# HalfBridge_MOSFET.net
KiCad netlist of a schematic drawn in Altium Designer
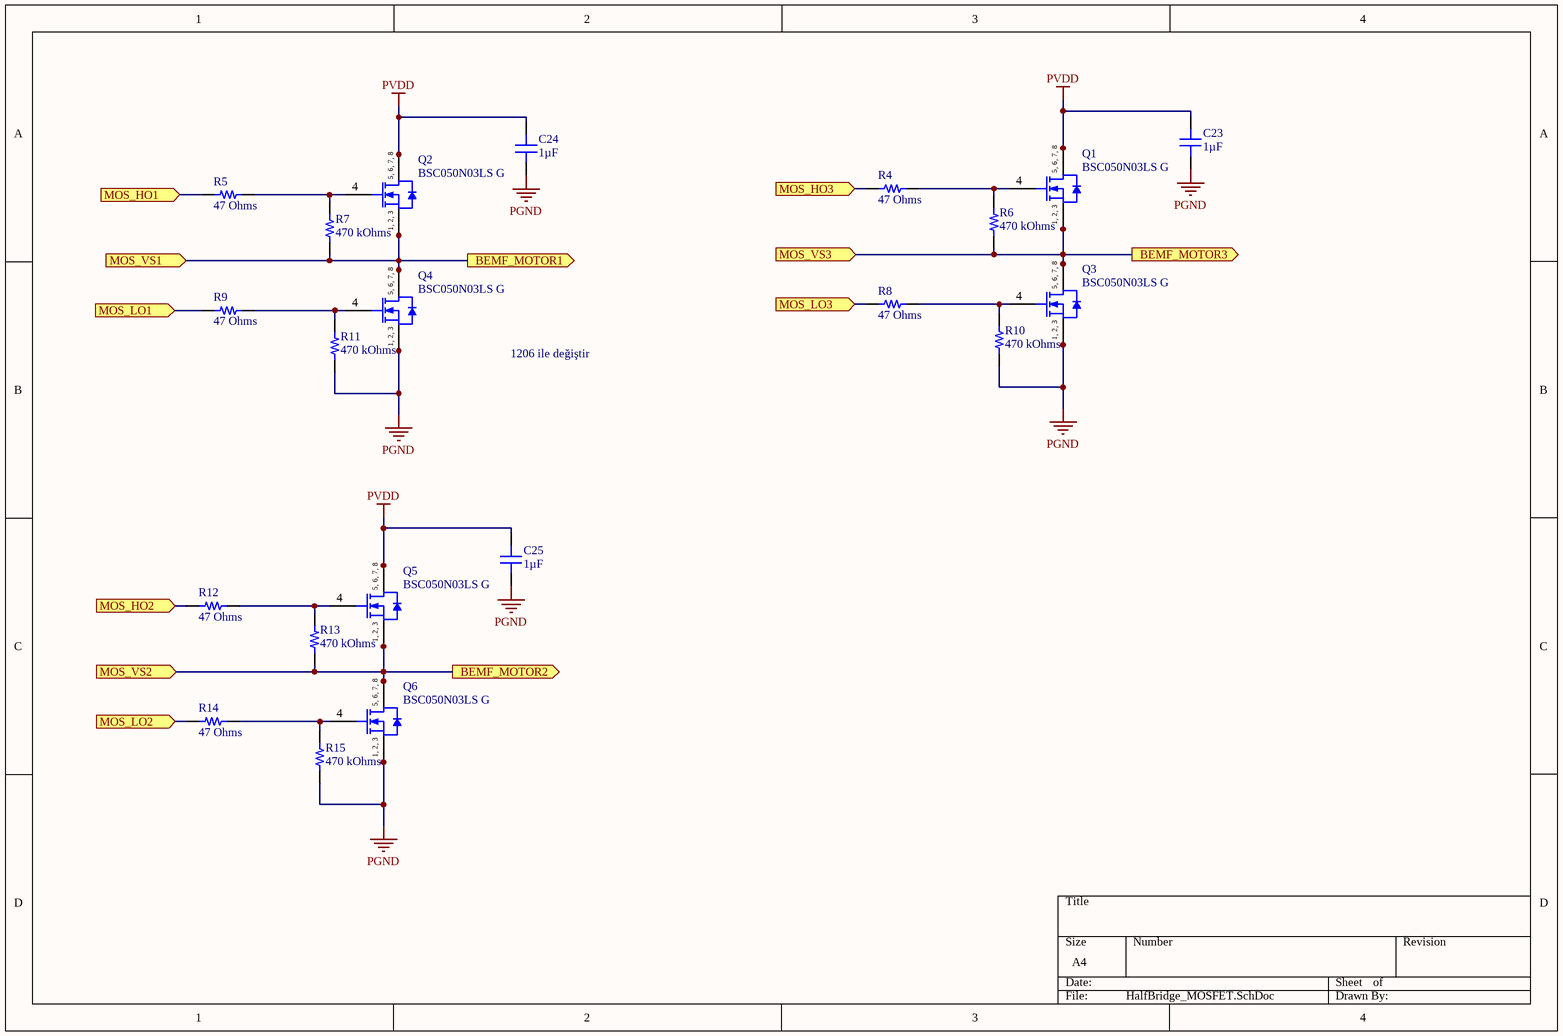
[diagram p0: HalfBridge_MOSFET.SchDoc]

(export (version "E")
  (design (tool "Eeschema 10.0.6"))
  (components
    (comp (ref "C23")
      (value "1µF")
      (footprint "CAP 1206_3216 - 1.8MM")
      (description "CAP CER 1UF 100V X7R 1206")
      (fields (field (name "PART NUMBER") "HMK316B7105KLHT") (field (name "MANUFACTURER") "Taiyo Yuden"))
      (libsource (lib "Celestial Altium Library - altium_library") (part "Capacitor"))
    )
    (comp (ref "C24")
      (value "1µF")
      (footprint "CAP 1206_3216 - 1.8MM")
      (description "CAP CER 1UF 100V X7R 1206")
      (fields (field (name "PART NUMBER") "HMK316B7105KLHT") (field (name "MANUFACTURER") "Taiyo Yuden"))
      (libsource (lib "Celestial Altium Library - altium_library") (part "Capacitor"))
    )
    (comp (ref "C25")
      (value "1µF")
      (footprint "CAP 1206_3216 - 1.8MM")
      (description "CAP CER 1UF 100V X7R 1206")
      (fields (field (name "PART NUMBER") "HMK316B7105KLHT") (field (name "MANUFACTURER") "Taiyo Yuden"))
      (libsource (lib "Celestial Altium Library - altium_library") (part "Capacitor"))
    )
    (comp (ref "Q1")
      (value "BSC050N03LS G")
      (footprint "INF-PG-TDSON-8-1_V")
      (description "N-Channel OptiMOS 3 Power-MOSFET, 30 V VDS, 79 A ID, -55 to 150 degC, PG-TDSON-8-1, Reel, Green")
      (fields (field (name "MANUFACTURER") "Infineon"))
      (libsource (lib "UserIntegrated") (part "BSC050N03LS G_1"))
    )
    (comp (ref "Q2")
      (value "BSC050N03LS G")
      (footprint "INF-PG-TDSON-8-1_V")
      (description "N-Channel OptiMOS 3 Power-MOSFET, 30 V VDS, 79 A ID, -55 to 150 degC, PG-TDSON-8-1, Reel, Green")
      (fields (field (name "MANUFACTURER") "Infineon"))
      (libsource (lib "UserIntegrated") (part "BSC050N03LS G_1"))
    )
    (comp (ref "Q3")
      (value "BSC050N03LS G")
      (footprint "INF-PG-TDSON-8-1_V")
      (description "N-Channel OptiMOS 3 Power-MOSFET, 30 V VDS, 79 A ID, -55 to 150 degC, PG-TDSON-8-1, Reel, Green")
      (fields (field (name "MANUFACTURER") "Infineon"))
      (libsource (lib "UserIntegrated") (part "BSC050N03LS G_1"))
    )
    (comp (ref "Q4")
      (value "BSC050N03LS G")
      (footprint "INF-PG-TDSON-8-1_V")
      (description "N-Channel OptiMOS 3 Power-MOSFET, 30 V VDS, 79 A ID, -55 to 150 degC, PG-TDSON-8-1, Reel, Green")
      (fields (field (name "MANUFACTURER") "Infineon"))
      (libsource (lib "UserIntegrated") (part "BSC050N03LS G_1"))
    )
    (comp (ref "Q5")
      (value "BSC050N03LS G")
      (footprint "INF-PG-TDSON-8-1_V")
      (description "N-Channel OptiMOS 3 Power-MOSFET, 30 V VDS, 79 A ID, -55 to 150 degC, PG-TDSON-8-1, Reel, Green")
      (fields (field (name "MANUFACTURER") "Infineon"))
      (libsource (lib "UserIntegrated") (part "BSC050N03LS G_1"))
    )
    (comp (ref "Q6")
      (value "BSC050N03LS G")
      (footprint "INF-PG-TDSON-8-1_V")
      (description "N-Channel OptiMOS 3 Power-MOSFET, 30 V VDS, 79 A ID, -55 to 150 degC, PG-TDSON-8-1, Reel, Green")
      (fields (field (name "MANUFACTURER") "Infineon"))
      (libsource (lib "UserIntegrated") (part "BSC050N03LS G_1"))
    )
    (comp (ref "R4")
      (value "47 Ohms")
      (footprint "RES 1206_3216")
      (description "RES SMD 47 OHM 5% 1/4W 1206")
      (fields (field (name "PART NUMBER") "CRCW120647R0JNEAIF") (field (name "MANUFACTURER") "Vishay Dale"))
      (libsource (lib "Celestial Altium Library - altium_library") (part "Resistor"))
    )
    (comp (ref "R5")
      (value "47 Ohms")
      (footprint "RES 1206_3216")
      (description "RES SMD 47 OHM 5% 1/4W 1206")
      (fields (field (name "PART NUMBER") "CRCW120647R0JNEAIF") (field (name "MANUFACTURER") "Vishay Dale"))
      (libsource (lib "Celestial Altium Library - altium_library") (part "Resistor"))
    )
    (comp (ref "R6")
      (value "470 kOhms")
      (footprint "RES 1206_3216")
      (description "RES SMD 470K OHM 1% 1/4W 1206")
      (fields (field (name "PART NUMBER") "CRCW1206470KFKEA") (field (name "MANUFACTURER") "Vishay Dale"))
      (libsource (lib "Celestial Altium Library - altium_library") (part "Resistor"))
    )
    (comp (ref "R7")
      (value "470 kOhms")
      (footprint "RES 1206_3216")
      (description "RES SMD 470K OHM 1% 1/4W 1206")
      (fields (field (name "PART NUMBER") "CRCW1206470KFKEA") (field (name "MANUFACTURER") "Vishay Dale"))
      (libsource (lib "Celestial Altium Library - altium_library") (part "Resistor"))
    )
    (comp (ref "R8")
      (value "47 Ohms")
      (footprint "RES 1206_3216")
      (description "RES SMD 47 OHM 5% 1/4W 1206")
      (fields (field (name "PART NUMBER") "CRCW120647R0JNEAIF") (field (name "MANUFACTURER") "Vishay Dale"))
      (libsource (lib "Celestial Altium Library - altium_library") (part "Resistor"))
    )
    (comp (ref "R9")
      (value "47 Ohms")
      (footprint "RES 1206_3216")
      (description "RES SMD 47 OHM 5% 1/4W 1206")
      (fields (field (name "PART NUMBER") "CRCW120647R0JNEAIF") (field (name "MANUFACTURER") "Vishay Dale"))
      (libsource (lib "Celestial Altium Library - altium_library") (part "Resistor"))
    )
    (comp (ref "R10")
      (value "470 kOhms")
      (footprint "RES 1206_3216")
      (description "RES SMD 470K OHM 1% 1/4W 1206")
      (fields (field (name "PART NUMBER") "CRCW1206470KFKEA") (field (name "MANUFACTURER") "Vishay Dale"))
      (libsource (lib "Celestial Altium Library - altium_library") (part "Resistor"))
    )
    (comp (ref "R11")
      (value "470 kOhms")
      (footprint "RES 1206_3216")
      (description "RES SMD 470K OHM 1% 1/4W 1206")
      (fields (field (name "PART NUMBER") "CRCW1206470KFKEA") (field (name "MANUFACTURER") "Vishay Dale"))
      (libsource (lib "Celestial Altium Library - altium_library") (part "Resistor"))
    )
    (comp (ref "R12")
      (value "47 Ohms")
      (footprint "RES 1206_3216")
      (description "RES SMD 47 OHM 5% 1/4W 1206")
      (fields (field (name "PART NUMBER") "CRCW120647R0JNEAIF") (field (name "MANUFACTURER") "Vishay Dale"))
      (libsource (lib "Celestial Altium Library - altium_library") (part "Resistor"))
    )
    (comp (ref "R13")
      (value "470 kOhms")
      (footprint "RES 1206_3216")
      (description "RES SMD 470K OHM 1% 1/4W 1206")
      (fields (field (name "PART NUMBER") "CRCW1206470KFKEA") (field (name "MANUFACTURER") "Vishay Dale"))
      (libsource (lib "Celestial Altium Library - altium_library") (part "Resistor"))
    )
    (comp (ref "R14")
      (value "47 Ohms")
      (footprint "RES 1206_3216")
      (description "RES SMD 47 OHM 5% 1/4W 1206")
      (fields (field (name "PART NUMBER") "CRCW120647R0JNEAIF") (field (name "MANUFACTURER") "Vishay Dale"))
      (libsource (lib "Celestial Altium Library - altium_library") (part "Resistor"))
    )
    (comp (ref "R15")
      (value "470 kOhms")
      (footprint "RES 1206_3216")
      (description "RES SMD 470K OHM 1% 1/4W 1206")
      (fields (field (name "PART NUMBER") "CRCW1206470KFKEA") (field (name "MANUFACTURER") "Vishay Dale"))
      (libsource (lib "Celestial Altium Library - altium_library") (part "Resistor"))
    )
  )
  (nets
    (net (code "1") (name "/BEMF_MOTOR1") (class "Default")
      (node (ref "Q2") (pin "1") (pinfunction "SOURCE_1") (pintype "passive"))
      (node (ref "Q2") (pin "2") (pinfunction "SOURCE_2") (pintype "passive"))
      (node (ref "Q2") (pin "3") (pinfunction "SOURCE_3") (pintype "passive"))
      (node (ref "Q4") (pin "5") (pinfunction "DRAIN_5") (pintype "passive"))
      (node (ref "Q4") (pin "6") (pinfunction "DRAIN_6") (pintype "passive"))
      (node (ref "Q4") (pin "7") (pinfunction "DRAIN_7") (pintype "passive"))
      (node (ref "Q4") (pin "8") (pinfunction "DRAIN_8") (pintype "passive"))
      (node (ref "R7") (pin "1") (pinfunction "1_1") (pintype "passive"))
    )
    (net (code "2") (name "/BEMF_MOTOR2") (class "Default")
      (node (ref "Q5") (pin "1") (pinfunction "SOURCE_1") (pintype "passive"))
      (node (ref "Q5") (pin "2") (pinfunction "SOURCE_2") (pintype "passive"))
      (node (ref "Q5") (pin "3") (pinfunction "SOURCE_3") (pintype "passive"))
      (node (ref "Q6") (pin "5") (pinfunction "DRAIN_5") (pintype "passive"))
      (node (ref "Q6") (pin "6") (pinfunction "DRAIN_6") (pintype "passive"))
      (node (ref "Q6") (pin "7") (pinfunction "DRAIN_7") (pintype "passive"))
      (node (ref "Q6") (pin "8") (pinfunction "DRAIN_8") (pintype "passive"))
      (node (ref "R13") (pin "1") (pinfunction "1_1") (pintype "passive"))
    )
    (net (code "3") (name "/BEMF_MOTOR3") (class "Default")
      (node (ref "Q1") (pin "1") (pinfunction "SOURCE_1") (pintype "passive"))
      (node (ref "Q1") (pin "2") (pinfunction "SOURCE_2") (pintype "passive"))
      (node (ref "Q1") (pin "3") (pinfunction "SOURCE_3") (pintype "passive"))
      (node (ref "Q3") (pin "5") (pinfunction "DRAIN_5") (pintype "passive"))
      (node (ref "Q3") (pin "6") (pinfunction "DRAIN_6") (pintype "passive"))
      (node (ref "Q3") (pin "7") (pinfunction "DRAIN_7") (pintype "passive"))
      (node (ref "Q3") (pin "8") (pinfunction "DRAIN_8") (pintype "passive"))
      (node (ref "R6") (pin "1") (pinfunction "1_1") (pintype "passive"))
    )
    (net (code "4") (name "/MOS_HO1") (class "Default")
      (node (ref "R5") (pin "1") (pinfunction "1_1") (pintype "passive"))
    )
    (net (code "5") (name "/MOS_HO2") (class "Default")
      (node (ref "R12") (pin "1") (pinfunction "1_1") (pintype "passive"))
    )
    (net (code "6") (name "/MOS_HO3") (class "Default")
      (node (ref "R4") (pin "1") (pinfunction "1_1") (pintype "passive"))
    )
    (net (code "7") (name "/MOS_LO1") (class "Default")
      (node (ref "R9") (pin "1") (pinfunction "1_1") (pintype "passive"))
    )
    (net (code "8") (name "/MOS_LO2") (class "Default")
      (node (ref "R14") (pin "1") (pinfunction "1_1") (pintype "passive"))
    )
    (net (code "9") (name "/MOS_LO3") (class "Default")
      (node (ref "R8") (pin "1") (pinfunction "1_1") (pintype "passive"))
    )
    (net (code "10") (name "Net-(Q1-GATE)") (class "Default")
      (node (ref "Q1") (pin "4") (pinfunction "GATE_4") (pintype "passive"))
      (node (ref "R4") (pin "2") (pinfunction "2_2") (pintype "passive"))
      (node (ref "R6") (pin "2") (pinfunction "2_2") (pintype "passive"))
    )
    (net (code "11") (name "Net-(Q2-GATE)") (class "Default")
      (node (ref "Q2") (pin "4") (pinfunction "GATE_4") (pintype "passive"))
      (node (ref "R5") (pin "2") (pinfunction "2_2") (pintype "passive"))
      (node (ref "R7") (pin "2") (pinfunction "2_2") (pintype "passive"))
    )
    (net (code "12") (name "Net-(Q3-GATE)") (class "Default")
      (node (ref "Q3") (pin "4") (pinfunction "GATE_4") (pintype "passive"))
      (node (ref "R10") (pin "2") (pinfunction "2_2") (pintype "passive"))
      (node (ref "R8") (pin "2") (pinfunction "2_2") (pintype "passive"))
    )
    (net (code "13") (name "Net-(Q4-GATE)") (class "Default")
      (node (ref "Q4") (pin "4") (pinfunction "GATE_4") (pintype "passive"))
      (node (ref "R11") (pin "2") (pinfunction "2_2") (pintype "passive"))
      (node (ref "R9") (pin "2") (pinfunction "2_2") (pintype "passive"))
    )
    (net (code "14") (name "Net-(Q5-GATE)") (class "Default")
      (node (ref "Q5") (pin "4") (pinfunction "GATE_4") (pintype "passive"))
      (node (ref "R12") (pin "2") (pinfunction "2_2") (pintype "passive"))
      (node (ref "R13") (pin "2") (pinfunction "2_2") (pintype "passive"))
    )
    (net (code "15") (name "Net-(Q6-GATE)") (class "Default")
      (node (ref "Q6") (pin "4") (pinfunction "GATE_4") (pintype "passive"))
      (node (ref "R14") (pin "2") (pinfunction "2_2") (pintype "passive"))
      (node (ref "R15") (pin "2") (pinfunction "2_2") (pintype "passive"))
    )
    (net (code "16") (name "PGND") (class "Default")
      (node (ref "C23") (pin "1") (pinfunction "1_1") (pintype "passive"))
      (node (ref "C24") (pin "1") (pinfunction "1_1") (pintype "passive"))
      (node (ref "C25") (pin "1") (pinfunction "1_1") (pintype "passive"))
      (node (ref "Q3") (pin "1") (pinfunction "SOURCE_1") (pintype "passive"))
      (node (ref "Q3") (pin "2") (pinfunction "SOURCE_2") (pintype "passive"))
      (node (ref "Q3") (pin "3") (pinfunction "SOURCE_3") (pintype "passive"))
      (node (ref "Q4") (pin "1") (pinfunction "SOURCE_1") (pintype "passive"))
      (node (ref "Q4") (pin "2") (pinfunction "SOURCE_2") (pintype "passive"))
      (node (ref "Q4") (pin "3") (pinfunction "SOURCE_3") (pintype "passive"))
      (node (ref "Q6") (pin "1") (pinfunction "SOURCE_1") (pintype "passive"))
      (node (ref "Q6") (pin "2") (pinfunction "SOURCE_2") (pintype "passive"))
      (node (ref "Q6") (pin "3") (pinfunction "SOURCE_3") (pintype "passive"))
      (node (ref "R10") (pin "1") (pinfunction "1_1") (pintype "passive"))
      (node (ref "R11") (pin "1") (pinfunction "1_1") (pintype "passive"))
      (node (ref "R15") (pin "1") (pinfunction "1_1") (pintype "passive"))
    )
    (net (code "17") (name "PVDD") (class "Default")
      (node (ref "C23") (pin "2") (pinfunction "2_2") (pintype "passive"))
      (node (ref "C24") (pin "2") (pinfunction "2_2") (pintype "passive"))
      (node (ref "C25") (pin "2") (pinfunction "2_2") (pintype "passive"))
      (node (ref "Q1") (pin "5") (pinfunction "DRAIN_5") (pintype "passive"))
      (node (ref "Q1") (pin "6") (pinfunction "DRAIN_6") (pintype "passive"))
      (node (ref "Q1") (pin "7") (pinfunction "DRAIN_7") (pintype "passive"))
      (node (ref "Q1") (pin "8") (pinfunction "DRAIN_8") (pintype "passive"))
      (node (ref "Q2") (pin "5") (pinfunction "DRAIN_5") (pintype "passive"))
      (node (ref "Q2") (pin "6") (pinfunction "DRAIN_6") (pintype "passive"))
      (node (ref "Q2") (pin "7") (pinfunction "DRAIN_7") (pintype "passive"))
      (node (ref "Q2") (pin "8") (pinfunction "DRAIN_8") (pintype "passive"))
      (node (ref "Q5") (pin "5") (pinfunction "DRAIN_5") (pintype "passive"))
      (node (ref "Q5") (pin "6") (pinfunction "DRAIN_6") (pintype "passive"))
      (node (ref "Q5") (pin "7") (pinfunction "DRAIN_7") (pintype "passive"))
      (node (ref "Q5") (pin "8") (pinfunction "DRAIN_8") (pintype "passive"))
    )
  )
)
